# ldr.net
KiCad netlist of a schematic drawn in EAGLE
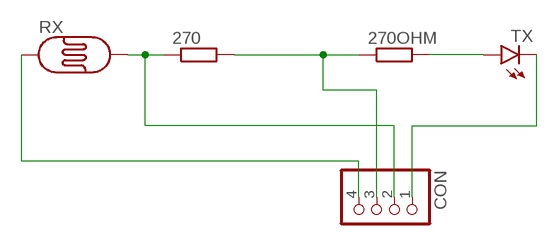
[diagram p0: schematic, sheet 1]

(export (version "E")
  (design (tool "Eeschema 10.0.6"))
  (components
    (comp (ref "270")
      (value "R-EU_0207/7")
      (footprint "eagle-import:0207_7")
      (libsource (lib "eagle-import") (part "R-EU_0207/7"))
    )
    (comp (ref "270OHM")
      (value "R-EU_0207/7")
      (footprint "eagle-import:0207_7")
      (libsource (lib "eagle-import") (part "R-EU_0207/7"))
    )
    (comp (ref "CON")
      (value "PINHD-1X4")
      (footprint "eagle-import:1X04")
      (libsource (lib "eagle-import") (part "PINHD-1X4"))
    )
    (comp (ref "RX")
      (value "PHOTOCELLONB")
      (footprint "eagle-import:ON_BOARD")
      (libsource (lib "eagle-import") (part "PHOTOCELLONB"))
    )
    (comp (ref "TX")
      (value "LED5MM")
      (footprint "eagle-import:LED5MM")
      (libsource (lib "eagle-import") (part "LED5MM"))
    )
  )
  (nets
    (net (code "1") (name "Net-(270-Pad2)") (class "Default")
      (node (ref "270") (pin "2") (pinfunction "2_2") (pintype "passive"))
      (node (ref "270OHM") (pin "1") (pinfunction "1_1") (pintype "passive"))
      (node (ref "CON") (pin "3") (pinfunction "3_3") (pintype "passive"))
    )
    (net (code "2") (name "Net-(270OHM-Pad2)") (class "Default")
      (node (ref "270OHM") (pin "2") (pinfunction "2_2") (pintype "passive"))
      (node (ref "TX") (pin "A") (pinfunction "A_A") (pintype "passive"))
    )
    (net (code "3") (name "Net-(RX-P$1)") (class "Default")
      (node (ref "CON") (pin "4") (pinfunction "4_4") (pintype "passive"))
      (node (ref "RX") (pin "1") (pinfunction "P$1_1") (pintype "bidirectional"))
    )
    (net (code "4") (name "Net-(RX-P$2)") (class "Default")
      (node (ref "270") (pin "1") (pinfunction "1_1") (pintype "passive"))
      (node (ref "CON") (pin "2") (pinfunction "2_2") (pintype "passive"))
      (node (ref "RX") (pin "2") (pinfunction "P$2_2") (pintype "bidirectional"))
    )
    (net (code "5") (name "Net-(TX-C)") (class "Default")
      (node (ref "CON") (pin "1") (pinfunction "1_1") (pintype "passive"))
      (node (ref "TX") (pin "K") (pinfunction "C_K") (pintype "passive"))
    )
  )
)
